# OnOnfre_Easy_Light_dev.net
KiCad netlist of a schematic drawn in EAGLE
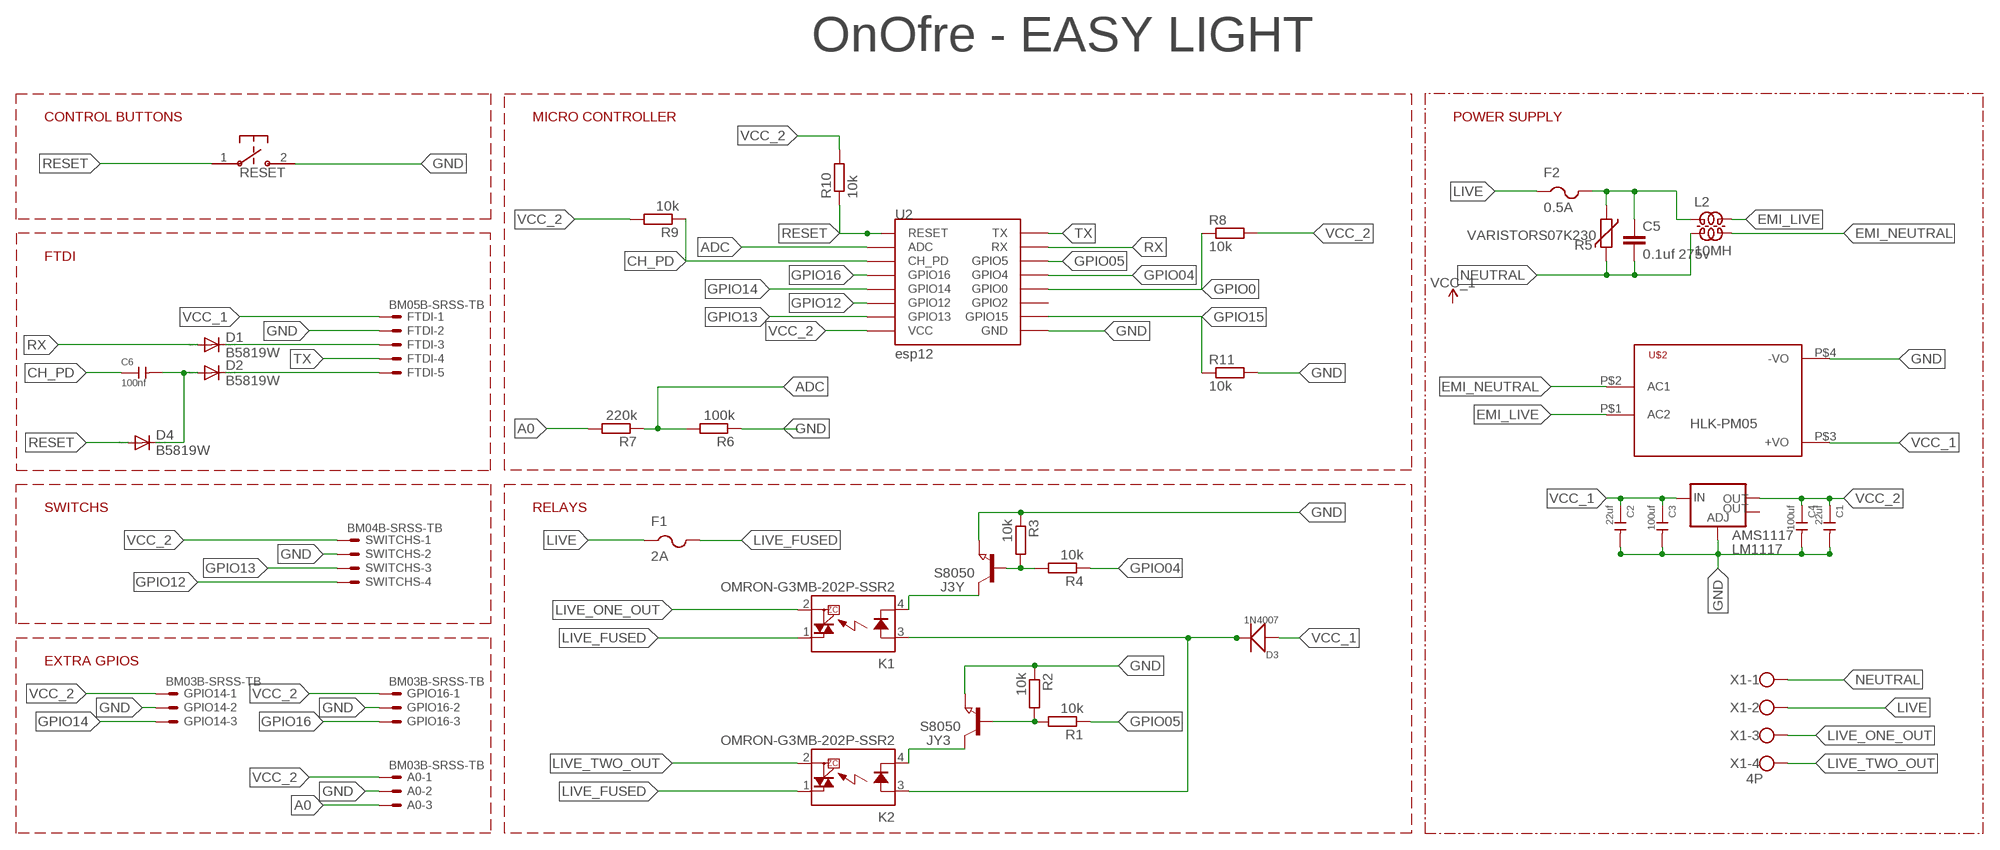
[diagram p0: schematic, sheet 1]

(export (version "E")
  (design (tool "Eeschema 10.0.6"))
  (components
    (comp (ref "A0")
      (value "BM03B-SRSS-TB")
      (footprint "eagle-import:BM03B-SRSS-TB")
      (libsource (lib "eagle-import") (part "?M03B-SRSS-TBB"))
    )
    (comp (ref "AMS1117")
      (value "LM1117")
      (footprint "eagle-import:SOT223")
      (libsource (lib "eagle-import") (part "V_REG_LM1117SOT223"))
    )
    (comp (ref "C1")
      (value "22uf")
      (footprint "eagle-import:C1206")
      (fields (field (name "MPN") "CC1206KKX7RCBB102"))
      (libsource (lib "eagle-import") (part "CERAMIC-1NF-1KV-10%-X7R?(1206)"))
    )
    (comp (ref "C2")
      (value "22uf")
      (footprint "eagle-import:C1206")
      (fields (field (name "MPN") "CC1206KKX7RCBB102"))
      (libsource (lib "eagle-import") (part "CERAMIC-1NF-1KV-10%-X7R?(1206)"))
    )
    (comp (ref "C3")
      (value "100uf")
      (footprint "eagle-import:C1206")
      (fields (field (name "MPN") "CC1206KKX7RCBB102"))
      (libsource (lib "eagle-import") (part "CERAMIC-1NF-1KV-10%-X7R?(1206)"))
    )
    (comp (ref "C4")
      (value "100uf")
      (footprint "eagle-import:C1206")
      (fields (field (name "MPN") "CC1206KKX7RCBB102"))
      (libsource (lib "eagle-import") (part "CERAMIC-1NF-1KV-10%-X7R?(1206)"))
    )
    (comp (ref "C5")
      (value "0.1uf 275v")
      (footprint "eagle-import:C102-054X133")
      (libsource (lib "eagle-import") (part "C-EU102-054X133"))
    )
    (comp (ref "C6")
      (value "100nf")
      (footprint "eagle-import:C0603")
      (fields (field (name "MPN") "CC0603KRX7R9BB104"))
      (libsource (lib "eagle-import") (part "CERAMIC-100NF-50V-10%-X7R(0603)"))
    )
    (comp (ref "D1")
      (value "B5819W")
      (footprint "eagle-import:SOD323-R")
      (libsource (lib "eagle-import") (part "DIODE-SOD323-R"))
    )
    (comp (ref "D2")
      (value "B5819W")
      (footprint "eagle-import:SOD323-R")
      (libsource (lib "eagle-import") (part "DIODE-SOD323-R"))
    )
    (comp (ref "D3")
      (value "1N4007")
      (footprint "eagle-import:DO-214AC")
      (libsource (lib "eagle-import") (part "DIODE-GEN-PURPOSE-1KV-1A(DO-214AC)"))
    )
    (comp (ref "D4")
      (value "B5819W")
      (footprint "eagle-import:SOD323-R")
      (libsource (lib "eagle-import") (part "DIODE-SOD323-R"))
    )
    (comp (ref "F1")
      (value "2A")
      (footprint "eagle-import:1812")
      (libsource (lib "eagle-import") (part "PTCFUSE-1812"))
    )
    (comp (ref "F2")
      (value "0.5A")
      (footprint "eagle-import:1812")
      (libsource (lib "eagle-import") (part "PTCFUSE-1812"))
    )
    (comp (ref "FTDI")
      (value "BM05B-SRSS-TB")
      (footprint "eagle-import:BM05B-SRSS-TB")
      (libsource (lib "eagle-import") (part "?M05B-SRSS-TBB"))
    )
    (comp (ref "GPIO14")
      (value "BM03B-SRSS-TB")
      (footprint "eagle-import:BM03B-SRSS-TB")
      (libsource (lib "eagle-import") (part "?M03B-SRSS-TBB"))
    )
    (comp (ref "GPIO16")
      (value "BM03B-SRSS-TB")
      (footprint "eagle-import:BM03B-SRSS-TB")
      (libsource (lib "eagle-import") (part "?M03B-SRSS-TBB"))
    )
    (comp (ref "J3Y")
      (value "S8050")
      (footprint "eagle-import:SOT23")
      (libsource (lib "eagle-import") (part "NPN-TRANSISTOR_SOT23"))
    )
    (comp (ref "JY3")
      (value "S8050")
      (footprint "eagle-import:SOT23")
      (libsource (lib "eagle-import") (part "NPN-TRANSISTOR_SOT23"))
    )
    (comp (ref "K1")
      (value "OMRON-G3MB-202P-SSR2")
      (footprint "eagle-import:OMRON-G3MB-202P-SSR")
      (fields (field (name "MPN") "S202S02F"))
      (libsource (lib "eagle-import") (part "OMRON-G3MB-202P-SSR2"))
    )
    (comp (ref "K2")
      (value "OMRON-G3MB-202P-SSR2")
      (footprint "eagle-import:OMRON-G3MB-202P-SSR")
      (fields (field (name "MPN") "S202S02F"))
      (libsource (lib "eagle-import") (part "OMRON-G3MB-202P-SSR2"))
    )
    (comp (ref "L2")
      (value "10MH")
      (footprint "eagle-import:ZD6-2X15")
      (libsource (lib "eagle-import") (part "ZD60820510"))
    )
    (comp (ref "R1")
      (value "10k")
      (footprint "eagle-import:R0603")
      (libsource (lib "eagle-import") (part "R-EU_R0603"))
    )
    (comp (ref "R2")
      (value "10k")
      (footprint "eagle-import:R0603")
      (libsource (lib "eagle-import") (part "R-EU_R0603"))
    )
    (comp (ref "R3")
      (value "10k")
      (footprint "eagle-import:R0603")
      (libsource (lib "eagle-import") (part "R-EU_R0603"))
    )
    (comp (ref "R4")
      (value "10k")
      (footprint "eagle-import:R0603")
      (libsource (lib "eagle-import") (part "R-EU_R0603"))
    )
    (comp (ref "R5")
      (value "VARISTORS07K230")
      (footprint "eagle-import:S07K230")
      (libsource (lib "eagle-import") (part "VARISTORS07K230"))
    )
    (comp (ref "R6")
      (value "100k")
      (footprint "eagle-import:R0603")
      (libsource (lib "eagle-import") (part "R-EU_R0603"))
    )
    (comp (ref "R7")
      (value "220k")
      (footprint "eagle-import:R0603")
      (libsource (lib "eagle-import") (part "R-EU_R0603"))
    )
    (comp (ref "R8")
      (value "10k")
      (footprint "eagle-import:R0603")
      (libsource (lib "eagle-import") (part "R-EU_R0603"))
    )
    (comp (ref "R9")
      (value "10k")
      (footprint "eagle-import:R0603")
      (libsource (lib "eagle-import") (part "R-EU_R0603"))
    )
    (comp (ref "R10")
      (value "10k")
      (footprint "eagle-import:R0603")
      (libsource (lib "eagle-import") (part "R-EU_R0603"))
    )
    (comp (ref "R11")
      (value "10k")
      (footprint "eagle-import:R0603")
      (libsource (lib "eagle-import") (part "R-EU_R0603"))
    )
    (comp (ref "RESET")
      (value "B3U-1000P-2P-SMD")
      (footprint "eagle-import:B3U-1000P")
      (fields (field (name "MANUFACTURER") "Omron") (field (name "MPN") "B3U-1000P"))
      (libsource (lib "eagle-import") (part "B3U-1000P"))
    )
    (comp (ref "SWITCHS")
      (value "BM04B-SRSS-TB")
      (footprint "eagle-import:BM04B-SRSS-TB")
      (libsource (lib "eagle-import") (part "?M04B-SRSS-TBB"))
    )
    (comp (ref "U$2")
      (value "HKLPM01")
      (footprint "eagle-import:HKLPM01")
      (libsource (lib "eagle-import") (part "HKLPM01"))
    )
    (comp (ref "U2")
      (value "esp12")
      (footprint "eagle-import:ESP12-SMD")
      (libsource (lib "eagle-import") (part "ESP12SMD"))
    )
    (comp (ref "X1")
      (value "4P")
      (footprint "eagle-import:W237-4")
      (libsource (lib "eagle-import") (part "W237-4"))
    )
  )
  (nets
    (net (code "1") (name "A0") (class "Default")
      (node (ref "A0") (pin "3") (pinfunction "S_3") (pintype "passive"))
      (node (ref "R7") (pin "2") (pinfunction "2_2") (pintype "passive"))
    )
    (net (code "2") (name "ADC") (class "Default")
      (node (ref "R6") (pin "2") (pinfunction "2_2") (pintype "passive"))
      (node (ref "R7") (pin "1") (pinfunction "1_1") (pintype "passive"))
      (node (ref "U2") (pin "ADC") (pinfunction "ADC_ADC") (pintype "bidirectional"))
    )
    (net (code "3") (name "CH_PD") (class "Default")
      (node (ref "C6") (pin "1") (pinfunction "1_1") (pintype "passive"))
      (node (ref "R9") (pin "1") (pinfunction "1_1") (pintype "passive"))
      (node (ref "U2") (pin "CH_PD") (pinfunction "CH_PD_CH_PD") (pintype "bidirectional"))
    )
    (net (code "4") (name "EMI_LIVE") (class "Default")
      (node (ref "L2") (pin "1") (pinfunction "4_1") (pintype "passive"))
      (node (ref "U$2") (pin "P$1") (pinfunction "AC2_P$1") (pintype "bidirectional"))
    )
    (net (code "5") (name "EMI_NEUTRAL") (class "Default")
      (node (ref "L2") (pin "2") (pinfunction "3_2") (pintype "passive"))
      (node (ref "U$2") (pin "P$2") (pinfunction "AC1_P$2") (pintype "bidirectional"))
    )
    (net (code "6") (name "GND") (class "Default")
      (node (ref "A0") (pin "2") (pinfunction "S_2") (pintype "passive"))
      (node (ref "AMS1117") (pin "1") (pinfunction "ADJ_1") (pintype "input"))
      (node (ref "C1") (pin "2") (pinfunction "2_2") (pintype "passive"))
      (node (ref "C2") (pin "2") (pinfunction "2_2") (pintype "passive"))
      (node (ref "C3") (pin "2") (pinfunction "2_2") (pintype "passive"))
      (node (ref "C4") (pin "2") (pinfunction "2_2") (pintype "passive"))
      (node (ref "FTDI") (pin "2") (pinfunction "S_2") (pintype "passive"))
      (node (ref "GPIO14") (pin "2") (pinfunction "S_2") (pintype "passive"))
      (node (ref "GPIO16") (pin "2") (pinfunction "S_2") (pintype "passive"))
      (node (ref "J3Y") (pin "2") (pinfunction "E_2") (pintype "passive"))
      (node (ref "JY3") (pin "2") (pinfunction "E_2") (pintype "passive"))
      (node (ref "R11") (pin "2") (pinfunction "2_2") (pintype "passive"))
      (node (ref "R2") (pin "1") (pinfunction "1_1") (pintype "passive"))
      (node (ref "R3") (pin "1") (pinfunction "1_1") (pintype "passive"))
      (node (ref "R6") (pin "1") (pinfunction "1_1") (pintype "passive"))
      (node (ref "RESET") (pin "2") (pinfunction "P$2_2") (pintype "passive"))
      (node (ref "SWITCHS") (pin "2") (pinfunction "S_2") (pintype "passive"))
      (node (ref "U$2") (pin "P$4") (pinfunction "-VO_P$4") (pintype "bidirectional"))
      (node (ref "U2") (pin "GND") (pinfunction "GND_GND") (pintype "bidirectional"))
    )
    (net (code "7") (name "GPIO0") (class "Default")
      (node (ref "R8") (pin "1") (pinfunction "1_1") (pintype "passive"))
      (node (ref "U2") (pin "GPIO0") (pinfunction "GPIO0_GPIO0") (pintype "bidirectional"))
    )
    (net (code "8") (name "GPIO04") (class "Default")
      (node (ref "R4") (pin "1") (pinfunction "1_1") (pintype "passive"))
      (node (ref "U2") (pin "GPIO4") (pinfunction "GPIO4_GPIO4") (pintype "bidirectional"))
    )
    (net (code "9") (name "GPIO05") (class "Default")
      (node (ref "R1") (pin "1") (pinfunction "1_1") (pintype "passive"))
      (node (ref "U2") (pin "GPIO5") (pinfunction "GPIO5_GPIO5") (pintype "bidirectional"))
    )
    (net (code "10") (name "GPIO12") (class "Default")
      (node (ref "SWITCHS") (pin "4") (pinfunction "S_4") (pintype "passive"))
      (node (ref "U2") (pin "GPIO12") (pinfunction "GPIO12_GPIO12") (pintype "bidirectional"))
    )
    (net (code "11") (name "GPIO13") (class "Default")
      (node (ref "SWITCHS") (pin "3") (pinfunction "S_3") (pintype "passive"))
      (node (ref "U2") (pin "GPIO13") (pinfunction "GPIO13_GPIO13") (pintype "bidirectional"))
    )
    (net (code "12") (name "GPIO14") (class "Default")
      (node (ref "GPIO14") (pin "3") (pinfunction "S_3") (pintype "passive"))
      (node (ref "U2") (pin "GPIO14") (pinfunction "GPIO14_GPIO14") (pintype "bidirectional"))
    )
    (net (code "13") (name "GPIO15") (class "Default")
      (node (ref "R11") (pin "1") (pinfunction "1_1") (pintype "passive"))
      (node (ref "U2") (pin "GPIO15") (pinfunction "GPIO15_GPIO15") (pintype "bidirectional"))
    )
    (net (code "14") (name "GPIO16") (class "Default")
      (node (ref "GPIO16") (pin "3") (pinfunction "S_3") (pintype "passive"))
      (node (ref "U2") (pin "GPIO16") (pinfunction "GPIO16_GPIO16") (pintype "bidirectional"))
    )
    (net (code "15") (name "LIVE") (class "Default")
      (node (ref "F1") (pin "1") (pinfunction "1_1") (pintype "passive"))
      (node (ref "F2") (pin "1") (pinfunction "1_1") (pintype "passive"))
      (node (ref "X1") (pin "2") (pinfunction "KL_2") (pintype "passive"))
    )
    (net (code "16") (name "LIVE_FUSED") (class "Default")
      (node (ref "F1") (pin "2") (pinfunction "2_2") (pintype "passive"))
      (node (ref "K1") (pin "1") (pinfunction "DS1_1") (pintype "passive"))
      (node (ref "K2") (pin "1") (pinfunction "DS1_1") (pintype "passive"))
    )
    (net (code "17") (name "LIVE_ONE_OUT") (class "Default")
      (node (ref "K1") (pin "2") (pinfunction "DS2_2") (pintype "passive"))
      (node (ref "X1") (pin "3") (pinfunction "KL_3") (pintype "passive"))
    )
    (net (code "18") (name "LIVE_TWO_OUT") (class "Default")
      (node (ref "K2") (pin "2") (pinfunction "DS2_2") (pintype "passive"))
      (node (ref "X1") (pin "4") (pinfunction "KL_4") (pintype "passive"))
    )
    (net (code "19") (name "NEUTRAL") (class "Default")
      (node (ref "C5") (pin "2") (pinfunction "2_2") (pintype "passive"))
      (node (ref "L2") (pin "3") (pinfunction "2_3") (pintype "passive"))
      (node (ref "R5") (pin "1") (pinfunction "1_1") (pintype "passive"))
      (node (ref "X1") (pin "1") (pinfunction "KL_1") (pintype "passive"))
    )
    (net (code "20") (name "Net-(C6-Pad2)") (class "Default")
      (node (ref "C6") (pin "2") (pinfunction "2_2") (pintype "passive"))
      (node (ref "D2") (pin "A") (pinfunction "A_A") (pintype "passive"))
      (node (ref "D4") (pin "C") (pinfunction "C_C") (pintype "passive"))
    )
    (net (code "21") (name "Net-(D3--)") (class "Default")
      (node (ref "D3") (pin "2") (pinfunction "-_2") (pintype "passive"))
      (node (ref "K1") (pin "3") (pinfunction "A_3") (pintype "passive"))
      (node (ref "K2") (pin "3") (pinfunction "A_3") (pintype "passive"))
    )
    (net (code "22") (name "Net-(FTDIC-S)") (class "Default")
      (node (ref "D1") (pin "C") (pinfunction "C_C") (pintype "passive"))
      (node (ref "FTDI") (pin "3") (pinfunction "S_3") (pintype "passive"))
    )
    (net (code "23") (name "Net-(FTDIE-S)") (class "Default")
      (node (ref "D2") (pin "C") (pinfunction "C_C") (pintype "passive"))
      (node (ref "FTDI") (pin "5") (pinfunction "S_5") (pintype "passive"))
    )
    (net (code "24") (name "Net-(J3Y-B)") (class "Default")
      (node (ref "J3Y") (pin "1") (pinfunction "B_1") (pintype "passive"))
      (node (ref "R3") (pin "2") (pinfunction "2_2") (pintype "passive"))
      (node (ref "R4") (pin "2") (pinfunction "2_2") (pintype "passive"))
    )
    (net (code "25") (name "Net-(J3Y-C)") (class "Default")
      (node (ref "J3Y") (pin "3") (pinfunction "C_3") (pintype "passive"))
      (node (ref "K1") (pin "4") (pinfunction "K_4") (pintype "passive"))
    )
    (net (code "26") (name "Net-(JY3-B)") (class "Default")
      (node (ref "JY3") (pin "1") (pinfunction "B_1") (pintype "passive"))
      (node (ref "R1") (pin "2") (pinfunction "2_2") (pintype "passive"))
      (node (ref "R2") (pin "2") (pinfunction "2_2") (pintype "passive"))
    )
    (net (code "27") (name "Net-(JY3-C)") (class "Default")
      (node (ref "JY3") (pin "3") (pinfunction "C_3") (pintype "passive"))
      (node (ref "K2") (pin "4") (pinfunction "K_4") (pintype "passive"))
    )
    (net (code "28") (name "Net-(L2-1)") (class "Default")
      (node (ref "C5") (pin "1") (pinfunction "1_1") (pintype "passive"))
      (node (ref "F2") (pin "2") (pinfunction "2_2") (pintype "passive"))
      (node (ref "L2") (pin "4") (pinfunction "1_4") (pintype "passive"))
      (node (ref "R5") (pin "2") (pinfunction "2_2") (pintype "passive"))
    )
    (net (code "29") (name "RESET") (class "Default")
      (node (ref "D4") (pin "A") (pinfunction "A_A") (pintype "passive"))
      (node (ref "R10") (pin "1") (pinfunction "1_1") (pintype "passive"))
      (node (ref "RESET") (pin "1") (pinfunction "P$1_1") (pintype "passive"))
      (node (ref "U2") (pin "RESET") (pinfunction "RESET_RESET") (pintype "bidirectional"))
    )
    (net (code "30") (name "RX") (class "Default")
      (node (ref "D1") (pin "A") (pinfunction "A_A") (pintype "passive"))
      (node (ref "U2") (pin "RXD0") (pinfunction "RX_RXD0") (pintype "bidirectional"))
    )
    (net (code "31") (name "TX") (class "Default")
      (node (ref "FTDI") (pin "4") (pinfunction "S_4") (pintype "passive"))
      (node (ref "U2") (pin "TXD0") (pinfunction "TX_TXD0") (pintype "bidirectional"))
    )
    (net (code "32") (name "VCC_1") (class "Default")
      (node (ref "AMS1117") (pin "3") (pinfunction "IN_3") (pintype "input"))
      (node (ref "C2") (pin "1") (pinfunction "1_1") (pintype "passive"))
      (node (ref "C3") (pin "1") (pinfunction "1_1") (pintype "passive"))
      (node (ref "D3") (pin "1") (pinfunction "+_1") (pintype "passive"))
      (node (ref "FTDI") (pin "1") (pinfunction "S_1") (pintype "passive"))
      (node (ref "U$2") (pin "P$3") (pinfunction "+VO_P$3") (pintype "bidirectional"))
    )
    (net (code "33") (name "VCC_2") (class "Default")
      (node (ref "A0") (pin "1") (pinfunction "S_1") (pintype "passive"))
      (node (ref "AMS1117") (pin "2") (pinfunction "OUT_2") (pintype "output"))
      (node (ref "C1") (pin "1") (pinfunction "1_1") (pintype "passive"))
      (node (ref "C4") (pin "1") (pinfunction "1_1") (pintype "passive"))
      (node (ref "GPIO14") (pin "1") (pinfunction "S_1") (pintype "passive"))
      (node (ref "GPIO16") (pin "1") (pinfunction "S_1") (pintype "passive"))
      (node (ref "R10") (pin "2") (pinfunction "2_2") (pintype "passive"))
      (node (ref "R8") (pin "2") (pinfunction "2_2") (pintype "passive"))
      (node (ref "R9") (pin "2") (pinfunction "2_2") (pintype "passive"))
      (node (ref "SWITCHS") (pin "1") (pinfunction "S_1") (pintype "passive"))
      (node (ref "U2") (pin "VCC") (pinfunction "VCC_VCC") (pintype "bidirectional"))
    )
    (net (code "34") (name "unconnected-(AMS1117-OUT-Pad4)") (class "Default")
      (node (ref "AMS1117") (pin "4") (pinfunction "OUT_4") (pintype "output"))
    )
    (net (code "35") (name "unconnected-(U2-PadGPIO2)") (class "Default")
      (node (ref "U2") (pin "GPIO2") (pinfunction "GPIO2_GPIO2") (pintype "bidirectional"))
    )
  )
)
